# DS139-1_0-B.net
KiCad netlist of a schematic drawn in Altium Designer
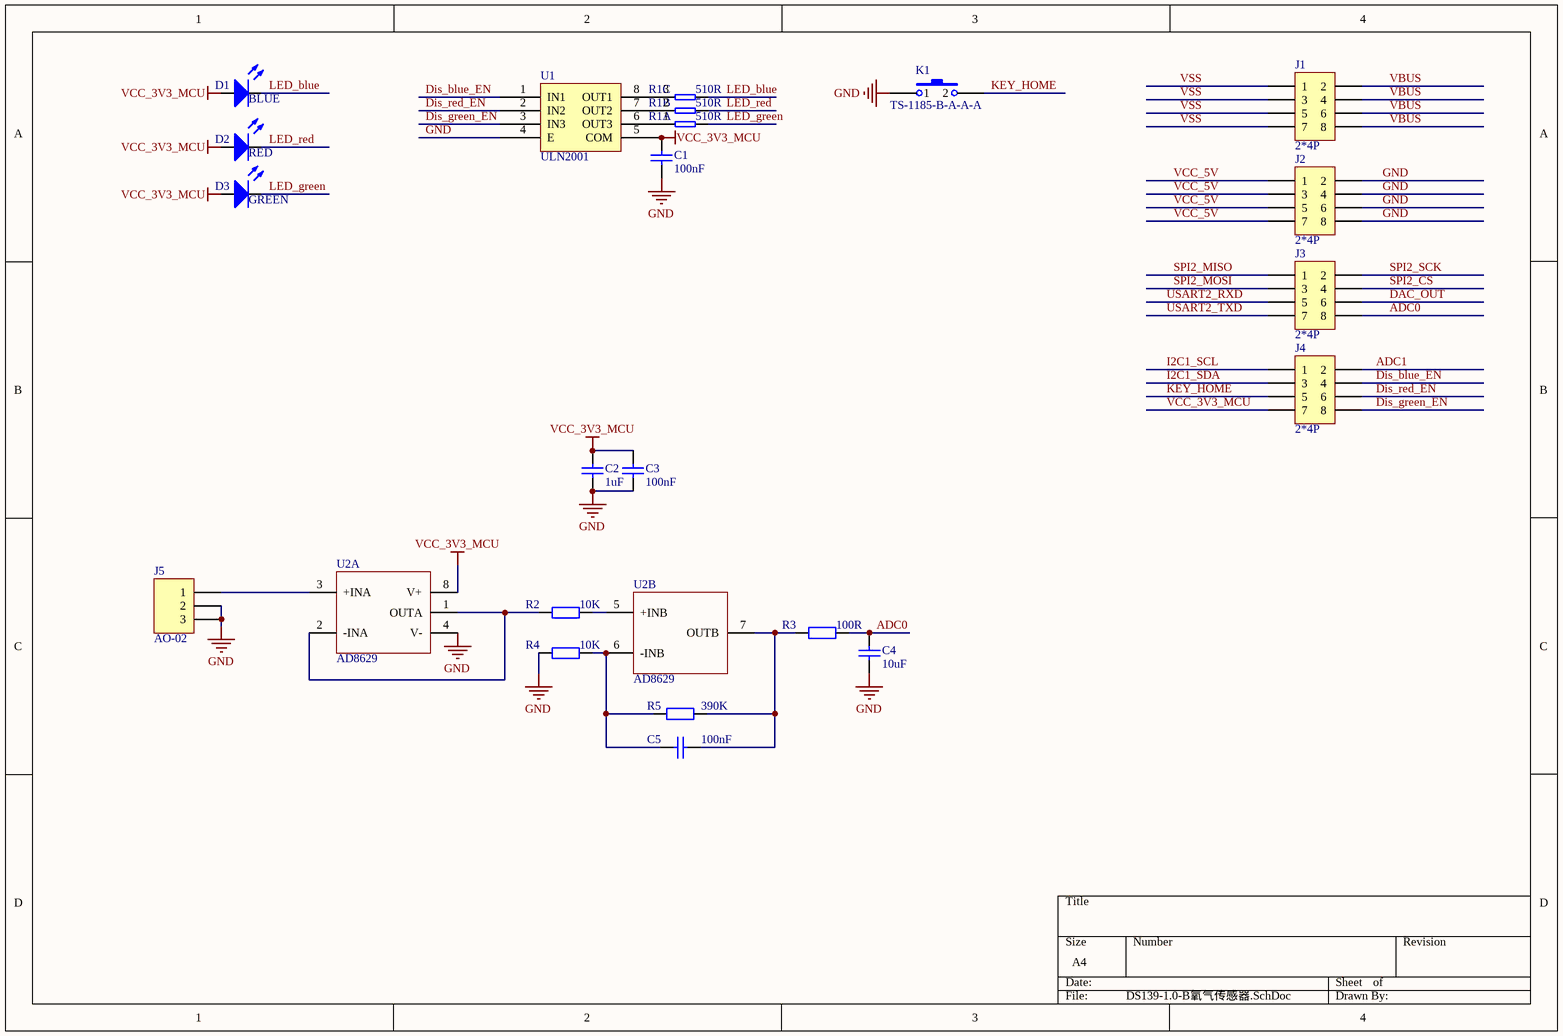
[diagram p0: DS139-1.0-B氧气传感器.SchDoc]

(export (version "E")
  (design (tool "Eeschema 10.0.6"))
  (components
    (comp (ref "C1")
      (value "100nF")
      (footprint "0603CAP")
      (description "贴片电容")
      (fields (field (name "Comment") "SMDCAP00013"))
      (libsource (lib "AD_SCH") (part "MLCC 100nF 50V ±10％ 0603"))
    )
    (comp (ref "C2")
      (value "1uF")
      (footprint "0603CAP")
      (description "贴片电容")
      (fields (field (name "Comment") "SMDCAP00015"))
      (libsource (lib "AD_SCH") (part "MLCC 1uF 50V ±10％ 0603"))
    )
    (comp (ref "C3")
      (value "100nF")
      (footprint "0603CAP")
      (description "贴片电容")
      (fields (field (name "Comment") "SMDCAP00013"))
      (libsource (lib "AD_SCH") (part "MLCC 100nF 50V ±10％ 0603"))
    )
    (comp (ref "C4")
      (value "10uF")
      (footprint "0603CAP")
      (description "贴片电容")
      (fields (field (name "Comment") "SMDCAP00016"))
      (libsource (lib "AD_SCH") (part "MLCC 10uF 50V ±10％ 0603"))
    )
    (comp (ref "C5")
      (value "100nF")
      (footprint "0603CAP")
      (description "贴片电容")
      (fields (field (name "Comment") "SMDCAP00013"))
      (libsource (lib "AD_SCH") (part "MLCC 100nF 50V ±10％ 0603"))
    )
    (comp (ref "D1")
      (value "BLUE")
      (footprint "LED_0805")
      (description "贴片LED")
      (fields (field (name "Comment") "SMDLED00010"))
      (libsource (lib "AD_SCH") (part "Chip 蓝色LED 0805"))
    )
    (comp (ref "D2")
      (value "RED")
      (footprint "LED_0805")
      (description "贴片LED")
      (fields (field (name "Comment") "SMDLED00003"))
      (libsource (lib "AD_SCH") (part "Chip 红色LED 0805"))
    )
    (comp (ref "D3")
      (value "GREEN")
      (footprint "LED_0805")
      (description "贴片LED")
      (fields (field (name "Comment") "Chip 翠绿LED 0805"))
      (libsource (lib "AD_SCH") (part "Chip 翠绿LED 0805"))
    )
    (comp (ref "J1")
      (value "2*4P")
      (footprint "X1321WVS-2x04J-C40D53")
      (description "双排针2x4P 立贴 1.27mm")
      (fields (field (name "Comment") "X1321WVS-2x04J-C40D53"))
      (libsource (lib "AD_SCH") (part "X1321WVS-2x04J-C40D53"))
    )
    (comp (ref "J2")
      (value "2*4P")
      (footprint "X1321WVS-2x04J-C40D53")
      (description "双排针2x4P 立贴 1.27mm")
      (fields (field (name "Comment") "X1321WVS-2x04J-C40D53"))
      (libsource (lib "AD_SCH") (part "X1321WVS-2x04J-C40D53"))
    )
    (comp (ref "J3")
      (value "2*4P")
      (footprint "X1321WVS-2x04J-C40D53")
      (description "双排针2x4P 立贴 1.27mm")
      (fields (field (name "Comment") "X1321WVS-2x04J-C40D53"))
      (libsource (lib "AD_SCH") (part "X1321WVS-2x04J-C40D53"))
    )
    (comp (ref "J4")
      (value "2*4P")
      (footprint "X1321WVS-2x04J-C40D53")
      (description "双排针2x4P 立贴 1.27mm")
      (fields (field (name "Comment") "X1321WVS-2x04J-C40D53"))
      (libsource (lib "AD_SCH") (part "X1321WVS-2x04J-C40D53"))
    )
    (comp (ref "J5")
      (value "AO-02")
      (footprint "SIP3")
      (description "单排直针")
      (fields (field (name "Comment") "SL000000042"))
      (libsource (lib "AD_SCH") (part "DIP3 单排直针 间距2.54mm 针长11mm 铜"))
    )
    (comp (ref "K1")
      (value "TS-1185-B-A-A-A")
      (footprint "KEY_TS-1185-x-A-A-A")
      (description "轻触开关")
      (libsource (lib "AD_SCH") (part "TS-1185-B-A-A-A"))
    )
    (comp (ref "R1")
      (value "510R")
      (footprint "0603RES_Pack4")
      (description "贴片排阻")
      (fields (field (name "Comment") "SMDRES05003"))
      (libsource (lib "AD_SCH") (part "Chip R*4 510R 1/16W ±5％ 0603"))
    )
    (comp (ref "R2")
      (value "10K")
      (footprint "0603RES")
      (description "贴片电阻")
      (fields (field (name "Comment") "SMDRES00056"))
      (libsource (lib "AD_SCH") (part "Chip 10K 1/16W ±1％ 0603"))
    )
    (comp (ref "R3")
      (value "100R")
      (footprint "0603RES")
      (description "贴片电阻")
      (fields (field (name "Comment") "SMDRES00015"))
      (libsource (lib "AD_SCH") (part "Chip 100R 1/16W ±1％ 0603"))
    )
    (comp (ref "R4")
      (value "10K")
      (footprint "0603RES")
      (description "贴片电阻")
      (fields (field (name "Comment") "SMDRES00056"))
      (libsource (lib "AD_SCH") (part "Chip 10K 1/16W ±1％ 0603"))
    )
    (comp (ref "R5")
      (value "390K")
      (footprint "0603RES")
      (description "贴片电阻")
      (fields (field (name "Comment") "SMDRES00079"))
      (libsource (lib "AD_SCH") (part "Chip 390K 1/16W ±1％ 0603"))
    )
    (comp (ref "U1")
      (value "ULN2001")
      (footprint "SO-8")
      (description "电机驱动芯片")
      (fields (field (name "Comment") "SMDIC000018"))
      (libsource (lib "AD_SCH") (part "ULN2001 SOP-8"))
    )
    (comp (ref "U2")
      (value "AD8629")
      (footprint "MSOP8")
      (description "失调电压 ：1μV\r\n输入失调漂移： 0.005μV/℃\r\n单电源：1.8-5.5V")
      (libsource (lib "AD_SCH") (part "AD8629"))
    )
  )
  (nets
    (net (code "1") (name "/ADC0") (class "Default")
      (node (ref "C4") (pin "2") (pinfunction "2_2") (pintype "passive"))
      (node (ref "J3") (pin "8") (pinfunction "8_8") (pintype "passive"))
      (node (ref "R3") (pin "2") (pinfunction "2_2") (pintype "passive"))
    )
    (net (code "2") (name "/ADC1") (class "Default")
      (node (ref "J4") (pin "2") (pinfunction "2_2") (pintype "passive"))
    )
    (net (code "3") (name "/DAC_OUT") (class "Default")
      (node (ref "J3") (pin "6") (pinfunction "6_6") (pintype "passive"))
    )
    (net (code "4") (name "/Dis_blue_EN") (class "Default")
      (node (ref "J4") (pin "4") (pinfunction "4_4") (pintype "passive"))
      (node (ref "U1") (pin "1") (pinfunction "IN1_1") (pintype "passive"))
    )
    (net (code "5") (name "/Dis_green_EN") (class "Default")
      (node (ref "J4") (pin "8") (pinfunction "8_8") (pintype "passive"))
      (node (ref "U1") (pin "3") (pinfunction "IN3_3") (pintype "passive"))
    )
    (net (code "6") (name "/Dis_red_EN") (class "Default")
      (node (ref "J4") (pin "6") (pinfunction "6_6") (pintype "passive"))
      (node (ref "U1") (pin "2") (pinfunction "IN2_2") (pintype "passive"))
    )
    (net (code "7") (name "/I2C1_SCL") (class "Default")
      (node (ref "J4") (pin "1") (pinfunction "1_1") (pintype "passive"))
    )
    (net (code "8") (name "/I2C1_SDA") (class "Default")
      (node (ref "J4") (pin "3") (pinfunction "3_3") (pintype "passive"))
    )
    (net (code "9") (name "/KEY_HOME") (class "Default")
      (node (ref "J4") (pin "5") (pinfunction "5_5") (pintype "passive"))
      (node (ref "K1") (pin "2") (pinfunction "2_2") (pintype "passive"))
    )
    (net (code "10") (name "/LED_blue") (class "Default")
      (node (ref "D1") (pin "2") (pinfunction "K_2") (pintype "passive"))
      (node (ref "R1") (pin "6") (pinfunction "6_6") (pintype "passive"))
    )
    (net (code "11") (name "/LED_green") (class "Default")
      (node (ref "D3") (pin "2") (pinfunction "K_2") (pintype "passive"))
      (node (ref "R1") (pin "8") (pinfunction "8_8") (pintype "passive"))
    )
    (net (code "12") (name "/LED_red") (class "Default")
      (node (ref "D2") (pin "2") (pinfunction "K_2") (pintype "passive"))
      (node (ref "R1") (pin "7") (pinfunction "7_7") (pintype "passive"))
    )
    (net (code "13") (name "/SPI2_CS") (class "Default")
      (node (ref "J3") (pin "4") (pinfunction "4_4") (pintype "passive"))
    )
    (net (code "14") (name "/SPI2_MISO") (class "Default")
      (node (ref "J3") (pin "1") (pinfunction "1_1") (pintype "passive"))
    )
    (net (code "15") (name "/SPI2_MOSI") (class "Default")
      (node (ref "J3") (pin "3") (pinfunction "3_3") (pintype "passive"))
    )
    (net (code "16") (name "/SPI2_SCK") (class "Default")
      (node (ref "J3") (pin "2") (pinfunction "2_2") (pintype "passive"))
    )
    (net (code "17") (name "/USART2_RXD") (class "Default")
      (node (ref "J3") (pin "5") (pinfunction "5_5") (pintype "passive"))
    )
    (net (code "18") (name "/USART2_TXD") (class "Default")
      (node (ref "J3") (pin "7") (pinfunction "7_7") (pintype "passive"))
    )
    (net (code "19") (name "/VBUS") (class "Default")
      (node (ref "J1") (pin "2") (pinfunction "2_2") (pintype "passive"))
      (node (ref "J1") (pin "4") (pinfunction "4_4") (pintype "passive"))
      (node (ref "J1") (pin "6") (pinfunction "6_6") (pintype "passive"))
      (node (ref "J1") (pin "8") (pinfunction "8_8") (pintype "passive"))
    )
    (net (code "20") (name "/VCC_5V") (class "Default")
      (node (ref "J2") (pin "1") (pinfunction "1_1") (pintype "passive"))
      (node (ref "J2") (pin "3") (pinfunction "3_3") (pintype "passive"))
      (node (ref "J2") (pin "5") (pinfunction "5_5") (pintype "passive"))
      (node (ref "J2") (pin "7") (pinfunction "7_7") (pintype "passive"))
    )
    (net (code "21") (name "/VSS") (class "Default")
      (node (ref "J1") (pin "1") (pinfunction "1_1") (pintype "passive"))
      (node (ref "J1") (pin "3") (pinfunction "3_3") (pintype "passive"))
      (node (ref "J1") (pin "5") (pinfunction "5_5") (pintype "passive"))
      (node (ref "J1") (pin "7") (pinfunction "7_7") (pintype "passive"))
    )
    (net (code "22") (name "GND") (class "Default")
      (node (ref "C1") (pin "1") (pinfunction "1_1") (pintype "passive"))
      (node (ref "C2") (pin "1") (pinfunction "1_1") (pintype "passive"))
      (node (ref "C3") (pin "1") (pinfunction "1_1") (pintype "passive"))
      (node (ref "C4") (pin "1") (pinfunction "1_1") (pintype "passive"))
      (node (ref "J2") (pin "2") (pinfunction "2_2") (pintype "passive"))
      (node (ref "J2") (pin "4") (pinfunction "4_4") (pintype "passive"))
      (node (ref "J2") (pin "6") (pinfunction "6_6") (pintype "passive"))
      (node (ref "J2") (pin "8") (pinfunction "8_8") (pintype "passive"))
      (node (ref "J5") (pin "2") (pinfunction "2_2") (pintype "passive"))
      (node (ref "J5") (pin "3") (pinfunction "3_3") (pintype "passive"))
      (node (ref "K1") (pin "1") (pinfunction "1_1") (pintype "passive"))
      (node (ref "R4") (pin "1") (pinfunction "1_1") (pintype "passive"))
      (node (ref "U1") (pin "4") (pinfunction "E_4") (pintype "passive"))
      (node (ref "U2") (pin "4") (pinfunction "V-_4") (pintype "passive"))
    )
    (net (code "23") (name "Net-(U1-OUT1)") (class "Default")
      (node (ref "R1") (pin "3") (pinfunction "3_3") (pintype "passive"))
      (node (ref "U1") (pin "8") (pinfunction "OUT1_8") (pintype "passive"))
    )
    (net (code "24") (name "Net-(U1-OUT2)") (class "Default")
      (node (ref "R1") (pin "2") (pinfunction "2_2") (pintype "passive"))
      (node (ref "U1") (pin "7") (pinfunction "OUT2_7") (pintype "passive"))
    )
    (net (code "25") (name "Net-(U1-OUT3)") (class "Default")
      (node (ref "R1") (pin "1") (pinfunction "1_1") (pintype "passive"))
      (node (ref "U1") (pin "6") (pinfunction "OUT3_6") (pintype "passive"))
    )
    (net (code "26") (name "Net-(U2A-+INA)") (class "Default")
      (node (ref "J5") (pin "1") (pinfunction "1_1") (pintype "passive"))
      (node (ref "U2") (pin "3") (pinfunction "+INA_3") (pintype "passive"))
    )
    (net (code "27") (name "Net-(U2A--INA)") (class "Default")
      (node (ref "R2") (pin "1") (pinfunction "1_1") (pintype "passive"))
      (node (ref "U2") (pin "1") (pinfunction "OUTA_1") (pintype "passive"))
      (node (ref "U2") (pin "2") (pinfunction "-INA_2") (pintype "passive"))
    )
    (net (code "28") (name "Net-(U2B-+INB)") (class "Default")
      (node (ref "R2") (pin "2") (pinfunction "2_2") (pintype "passive"))
      (node (ref "U2") (pin "5") (pinfunction "+INB_5") (pintype "passive"))
    )
    (net (code "29") (name "Net-(U2B--INB)") (class "Default")
      (node (ref "C5") (pin "1") (pinfunction "1_1") (pintype "passive"))
      (node (ref "R4") (pin "2") (pinfunction "2_2") (pintype "passive"))
      (node (ref "R5") (pin "1") (pinfunction "1_1") (pintype "passive"))
      (node (ref "U2") (pin "6") (pinfunction "-INB_6") (pintype "passive"))
    )
    (net (code "30") (name "Net-(U2B-OUTB)") (class "Default")
      (node (ref "C5") (pin "2") (pinfunction "2_2") (pintype "passive"))
      (node (ref "R3") (pin "1") (pinfunction "1_1") (pintype "passive"))
      (node (ref "R5") (pin "2") (pinfunction "2_2") (pintype "passive"))
      (node (ref "U2") (pin "7") (pinfunction "OUTB_7") (pintype "passive"))
    )
    (net (code "31") (name "VCC_3V3_MCU") (class "Default")
      (node (ref "C1") (pin "2") (pinfunction "2_2") (pintype "passive"))
      (node (ref "C2") (pin "2") (pinfunction "2_2") (pintype "passive"))
      (node (ref "C3") (pin "2") (pinfunction "2_2") (pintype "passive"))
      (node (ref "D1") (pin "1") (pinfunction "A_1") (pintype "passive"))
      (node (ref "D2") (pin "1") (pinfunction "A_1") (pintype "passive"))
      (node (ref "D3") (pin "1") (pinfunction "A_1") (pintype "passive"))
      (node (ref "J4") (pin "7") (pinfunction "7_7") (pintype "passive"))
      (node (ref "U1") (pin "5") (pinfunction "COM_5") (pintype "passive"))
      (node (ref "U2") (pin "8") (pinfunction "V+_8") (pintype "passive"))
    )
  )
)
